# PROC010C_HD_Connector.net
KiCad netlist of a schematic drawn in Altium Designer
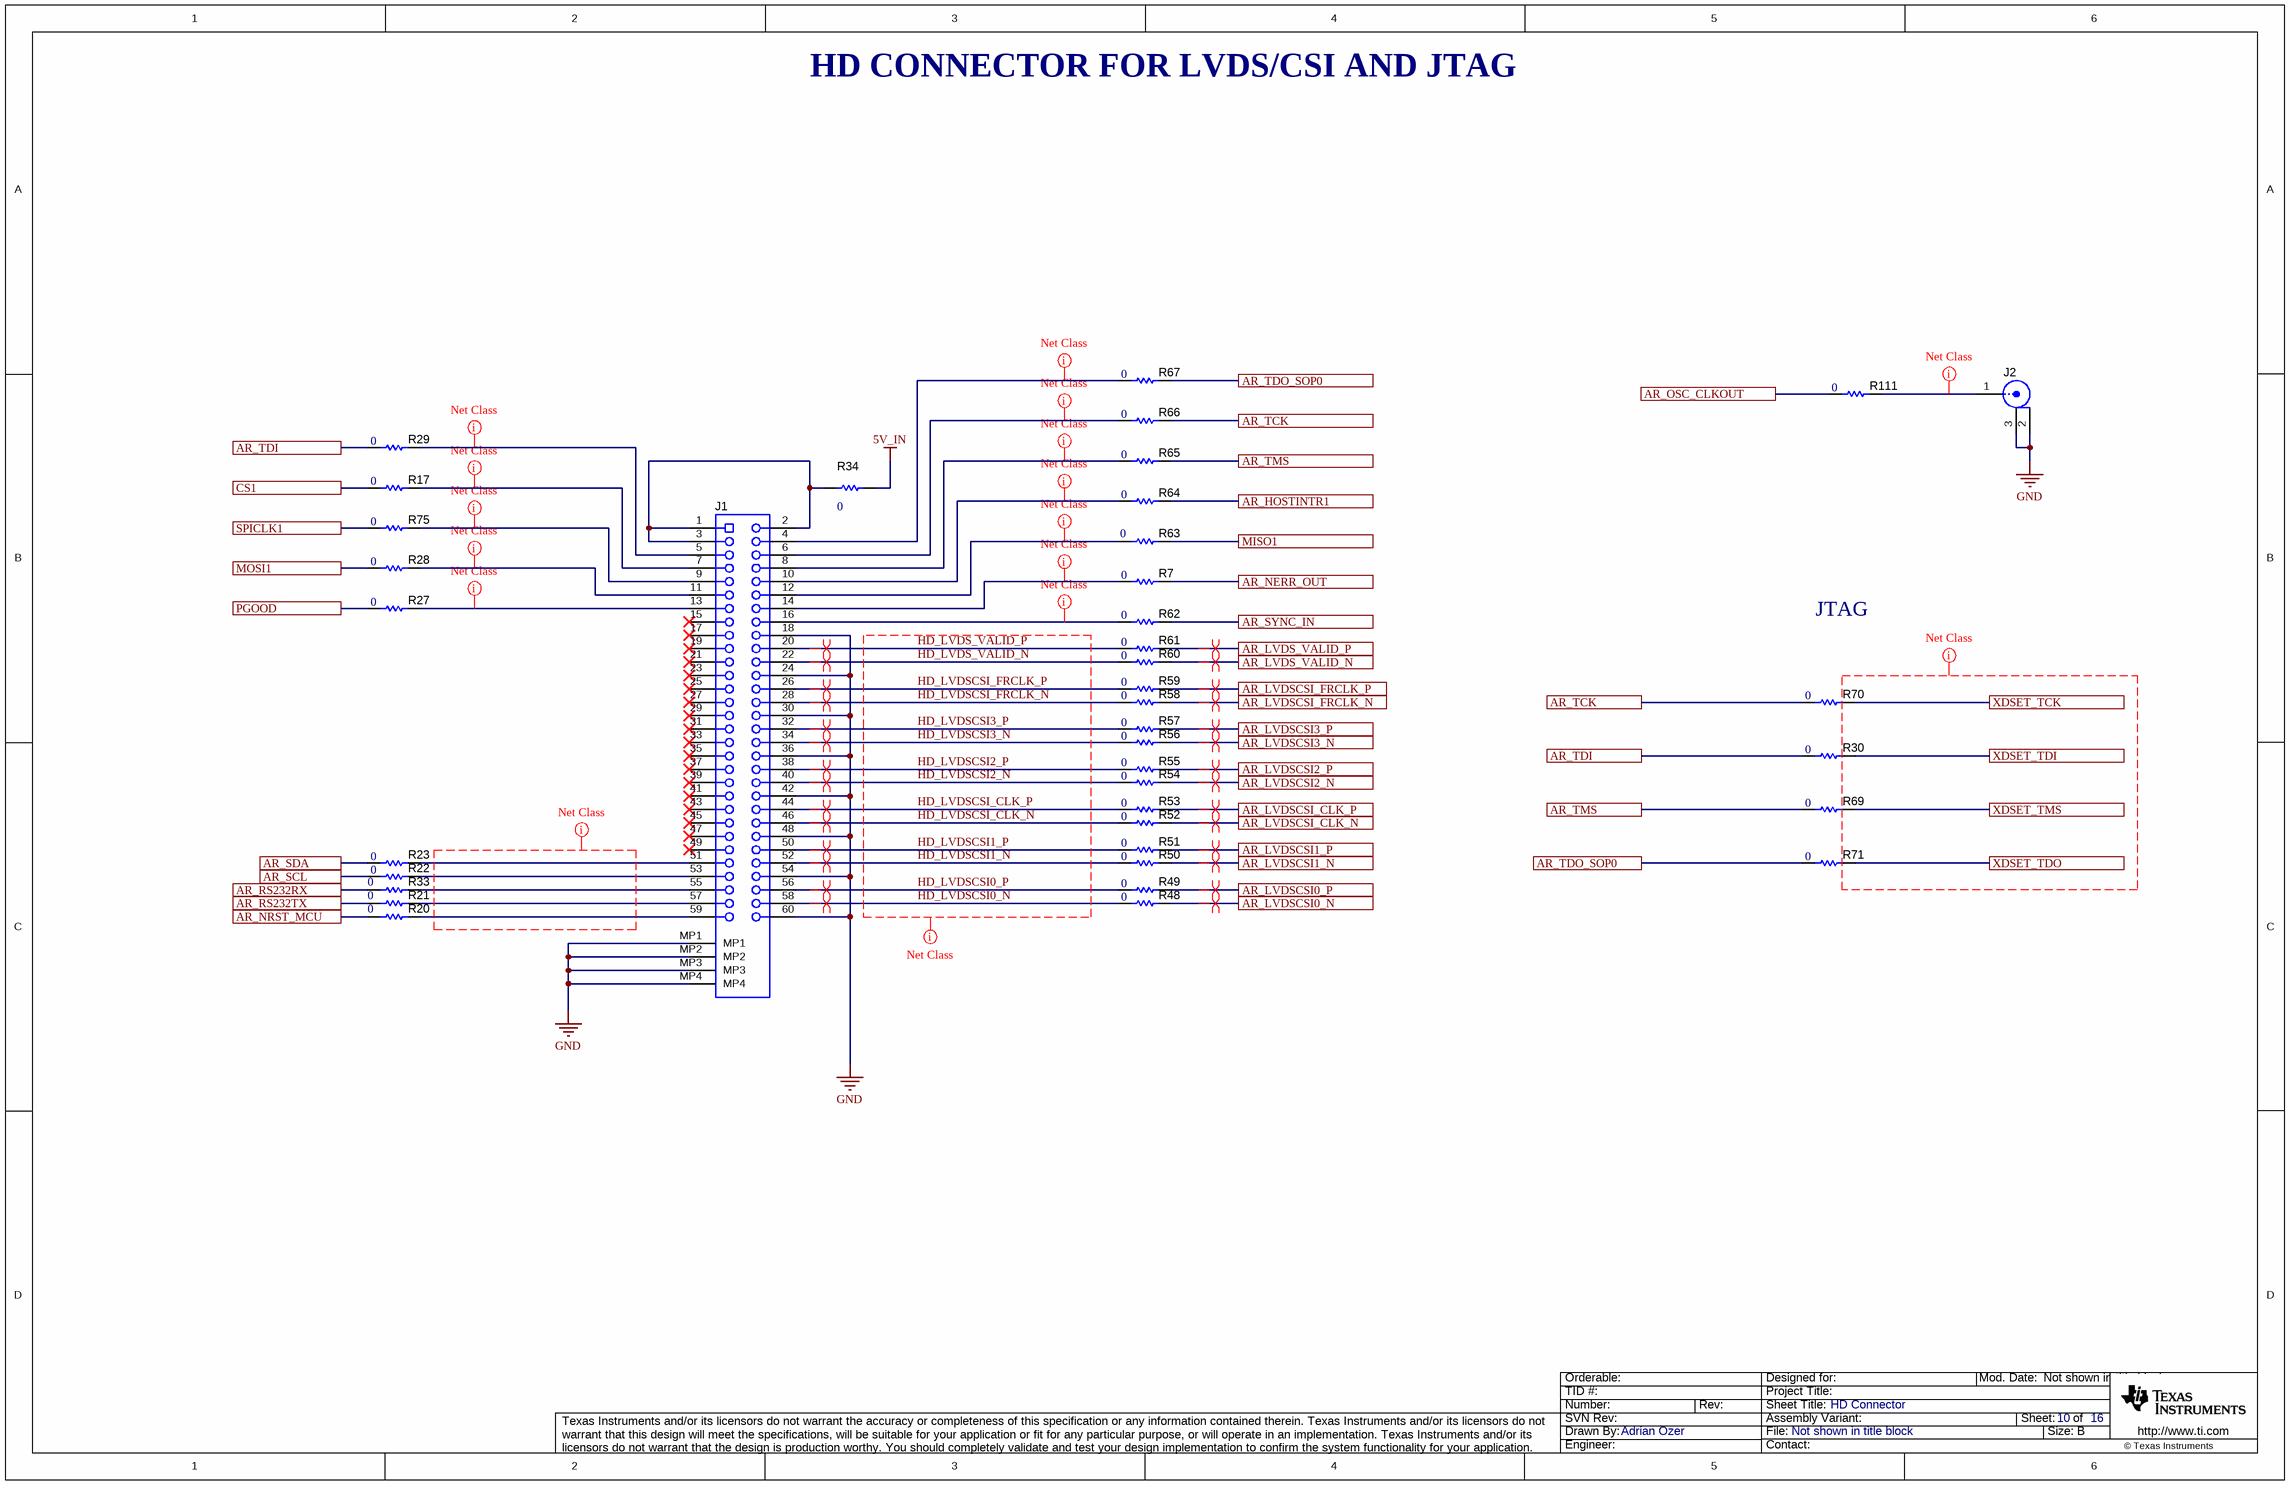
[diagram p0: PROC010C_HD Connector.SchDoc]

(export (version "E")
  (design (tool "Eeschema 10.0.6"))
  (components
    (comp (ref "J1")
      (value "QSH-030-01-L-D-A")
      (footprint "Samtec_QSH-030-01-X-D-A")
      (description "Receptacle, 0.5 mm, 30x2, Gold, TH")
      (fields (field (name "MANUFACTURER") "Samtec") (field (name "PUBLISHER") "Texas Instruments"))
      (libsource (lib "Altium Vault - TI") (part "Receptacle_30x2_4MP_LeftRight"))
    )
    (comp (ref "J2")
      (value "128-0711-201")
      (footprint "Johnson_128-0711-201")
      (description "UMC Straight Jack Receptacle, 50 Ohm, Gold, SMT")
      (fields
        (field (name "MANUFACTURER") "Cinch Connectivity")
        (field (name "PUBLISHER") "Texas Instruments")
      )
      (libsource (lib "Altium Vault - TI") (part "CMP-0055788-1"))
    )
    (comp (ref "R7")
      (value "CRCW02010000Z0ED")
      (footprint "0201_Silk")
      (description "RES, 0, 5%, 0.05 W, 0201")
      (fields (field (name "MANUFACTURER") "Vishay-Dale") (field (name "VALUEDISPLAYED") "0"))
      (libsource (lib "Altium Vault - TI") (part "Resistor"))
    )
    (comp (ref "R17")
      (value "CRCW02010000Z0ED")
      (footprint "0201_Silk")
      (description "RES, 0, 5%, 0.05 W, 0201")
      (fields (field (name "MANUFACTURER") "Vishay-Dale") (field (name "VALUEDISPLAYED") "0"))
      (libsource (lib "Altium Vault - TI") (part "Resistor"))
    )
    (comp (ref "R20")
      (value "CRCW02010000Z0ED")
      (footprint "0201_Silk")
      (description "RES, 0, 5%, 0.05 W, 0201")
      (fields (field (name "MANUFACTURER") "Vishay-Dale") (field (name "VALUEDISPLAYED") "0"))
      (libsource (lib "Altium Vault - TI") (part "Resistor"))
    )
    (comp (ref "R21")
      (value "CRCW02010000Z0ED")
      (footprint "0201_Silk")
      (description "RES, 0, 5%, 0.05 W, 0201")
      (fields (field (name "MANUFACTURER") "Vishay-Dale") (field (name "VALUEDISPLAYED") "0"))
      (libsource (lib "Altium Vault - TI") (part "Resistor"))
    )
    (comp (ref "R22")
      (value "CRCW02010000Z0ED")
      (footprint "0201_Silk")
      (description "RES, 0, 5%, 0.05 W, 0201")
      (fields (field (name "MANUFACTURER") "Vishay-Dale") (field (name "VALUEDISPLAYED") "0"))
      (libsource (lib "Altium Vault - TI") (part "Resistor"))
    )
    (comp (ref "R23")
      (value "CRCW02010000Z0ED")
      (footprint "0201_Silk")
      (description "RES, 0, 5%, 0.05 W, 0201")
      (fields (field (name "MANUFACTURER") "Vishay-Dale") (field (name "VALUEDISPLAYED") "0"))
      (libsource (lib "Altium Vault - TI") (part "Resistor"))
    )
    (comp (ref "R27")
      (value "CRCW02010000Z0ED")
      (footprint "0201_Silk")
      (description "RES, 0, 5%, 0.05 W, 0201")
      (fields (field (name "MANUFACTURER") "Vishay-Dale") (field (name "VALUEDISPLAYED") "0"))
      (libsource (lib "Altium Vault - TI") (part "Resistor"))
    )
    (comp (ref "R28")
      (value "CRCW02010000Z0ED")
      (footprint "0201_Silk")
      (description "RES, 0, 5%, 0.05 W, 0201")
      (fields (field (name "MANUFACTURER") "Vishay-Dale") (field (name "VALUEDISPLAYED") "0"))
      (libsource (lib "Altium Vault - TI") (part "Resistor"))
    )
    (comp (ref "R29")
      (value "CRCW02010000Z0ED")
      (footprint "0201_Silk")
      (description "RES, 0, 5%, 0.05 W, 0201")
      (fields (field (name "MANUFACTURER") "Vishay-Dale") (field (name "VALUEDISPLAYED") "0"))
      (libsource (lib "Altium Vault - TI") (part "Resistor"))
    )
    (comp (ref "R30")
      (value "CRCW02010000Z0ED")
      (footprint "0201_Silk")
      (description "RES, 0, 5%, 0.05 W, 0201")
      (fields (field (name "MANUFACTURER") "Vishay-Dale") (field (name "VALUEDISPLAYED") "0"))
      (libsource (lib "Altium Vault - TI") (part "Resistor"))
    )
    (comp (ref "R33")
      (value "CRCW02010000Z0ED")
      (footprint "0201_Silk")
      (description "RES, 0, 5%, 0.05 W, 0201")
      (fields (field (name "MANUFACTURER") "Vishay-Dale") (field (name "VALUEDISPLAYED") "0"))
      (libsource (lib "Altium Vault - TI") (part "Resistor"))
    )
    (comp (ref "R34")
      (value "CRCW20100000Z0EF")
      (footprint "2010L")
      (description "RES, 0, 5%, 0.75 W, AEC-Q200 Grade 0, 2010")
      (fields (field (name "MANUFACTURER") "Vishay-Dale") (field (name "VALUEDISPLAYED") "0"))
      (libsource (lib "Altium Vault - TI") (part "CMP-0016044-3"))
    )
    (comp (ref "R48")
      (value "CRCW02010000Z0ED")
      (footprint "0201_Silk")
      (description "RES, 0, 5%, 0.05 W, 0201")
      (fields (field (name "MANUFACTURER") "Vishay-Dale") (field (name "VALUEDISPLAYED") "0"))
      (libsource (lib "Altium Vault - TI") (part "Resistor"))
    )
    (comp (ref "R49")
      (value "CRCW02010000Z0ED")
      (footprint "0201_Silk")
      (description "RES, 0, 5%, 0.05 W, 0201")
      (fields (field (name "MANUFACTURER") "Vishay-Dale") (field (name "VALUEDISPLAYED") "0"))
      (libsource (lib "Altium Vault - TI") (part "Resistor"))
    )
    (comp (ref "R50")
      (value "CRCW02010000Z0ED")
      (footprint "0201_Silk")
      (description "RES, 0, 5%, 0.05 W, 0201")
      (fields (field (name "MANUFACTURER") "Vishay-Dale") (field (name "VALUEDISPLAYED") "0"))
      (libsource (lib "Altium Vault - TI") (part "Resistor"))
    )
    (comp (ref "R51")
      (value "CRCW02010000Z0ED")
      (footprint "0201_Silk")
      (description "RES, 0, 5%, 0.05 W, 0201")
      (fields (field (name "MANUFACTURER") "Vishay-Dale") (field (name "VALUEDISPLAYED") "0"))
      (libsource (lib "Altium Vault - TI") (part "Resistor"))
    )
    (comp (ref "R52")
      (value "CRCW02010000Z0ED")
      (footprint "0201_Silk")
      (description "RES, 0, 5%, 0.05 W, 0201")
      (fields (field (name "MANUFACTURER") "Vishay-Dale") (field (name "VALUEDISPLAYED") "0"))
      (libsource (lib "Altium Vault - TI") (part "Resistor"))
    )
    (comp (ref "R53")
      (value "CRCW02010000Z0ED")
      (footprint "0201_Silk")
      (description "RES, 0, 5%, 0.05 W, 0201")
      (fields (field (name "MANUFACTURER") "Vishay-Dale") (field (name "VALUEDISPLAYED") "0"))
      (libsource (lib "Altium Vault - TI") (part "Resistor"))
    )
    (comp (ref "R54")
      (value "CRCW02010000Z0ED")
      (footprint "0201_Silk")
      (description "RES, 0, 5%, 0.05 W, 0201")
      (fields (field (name "MANUFACTURER") "Vishay-Dale") (field (name "VALUEDISPLAYED") "0"))
      (libsource (lib "Altium Vault - TI") (part "Resistor"))
    )
    (comp (ref "R55")
      (value "CRCW02010000Z0ED")
      (footprint "0201_Silk")
      (description "RES, 0, 5%, 0.05 W, 0201")
      (fields (field (name "MANUFACTURER") "Vishay-Dale") (field (name "VALUEDISPLAYED") "0"))
      (libsource (lib "Altium Vault - TI") (part "Resistor"))
    )
    (comp (ref "R56")
      (value "CRCW02010000Z0ED")
      (footprint "0201_Silk")
      (description "RES, 0, 5%, 0.05 W, 0201")
      (fields (field (name "MANUFACTURER") "Vishay-Dale") (field (name "VALUEDISPLAYED") "0"))
      (libsource (lib "Altium Vault - TI") (part "Resistor"))
    )
    (comp (ref "R57")
      (value "CRCW02010000Z0ED")
      (footprint "0201_Silk")
      (description "RES, 0, 5%, 0.05 W, 0201")
      (fields (field (name "MANUFACTURER") "Vishay-Dale") (field (name "VALUEDISPLAYED") "0"))
      (libsource (lib "Altium Vault - TI") (part "Resistor"))
    )
    (comp (ref "R58")
      (value "CRCW02010000Z0ED")
      (footprint "0201_Silk")
      (description "RES, 0, 5%, 0.05 W, 0201")
      (fields (field (name "MANUFACTURER") "Vishay-Dale") (field (name "VALUEDISPLAYED") "0"))
      (libsource (lib "Altium Vault - TI") (part "Resistor"))
    )
    (comp (ref "R59")
      (value "CRCW02010000Z0ED")
      (footprint "0201_Silk")
      (description "RES, 0, 5%, 0.05 W, 0201")
      (fields (field (name "MANUFACTURER") "Vishay-Dale") (field (name "VALUEDISPLAYED") "0"))
      (libsource (lib "Altium Vault - TI") (part "Resistor"))
    )
    (comp (ref "R60")
      (value "CRCW02010000Z0ED")
      (footprint "0201_Silk")
      (description "RES, 0, 5%, 0.05 W, 0201")
      (fields (field (name "MANUFACTURER") "Vishay-Dale") (field (name "VALUEDISPLAYED") "0"))
      (libsource (lib "Altium Vault - TI") (part "Resistor"))
    )
    (comp (ref "R61")
      (value "CRCW02010000Z0ED")
      (footprint "0201_Silk")
      (description "RES, 0, 5%, 0.05 W, 0201")
      (fields (field (name "MANUFACTURER") "Vishay-Dale") (field (name "VALUEDISPLAYED") "0"))
      (libsource (lib "Altium Vault - TI") (part "Resistor"))
    )
    (comp (ref "R62")
      (value "CRCW02010000Z0ED")
      (footprint "0201_Silk")
      (description "RES, 0, 5%, 0.05 W, 0201")
      (fields (field (name "MANUFACTURER") "Vishay-Dale") (field (name "VALUEDISPLAYED") "0"))
      (libsource (lib "Altium Vault - TI") (part "Resistor"))
    )
    (comp (ref "R63")
      (value "CRCW02010000Z0ED")
      (footprint "0201_Silk")
      (description "RES, 0, 5%, 0.05 W, 0201")
      (fields (field (name "MANUFACTURER") "Vishay-Dale") (field (name "VALUEDISPLAYED") "0"))
      (libsource (lib "Altium Vault - TI") (part "Resistor"))
    )
    (comp (ref "R64")
      (value "CRCW02010000Z0ED")
      (footprint "0201_Silk")
      (description "RES, 0, 5%, 0.05 W, 0201")
      (fields (field (name "MANUFACTURER") "Vishay-Dale") (field (name "VALUEDISPLAYED") "0"))
      (libsource (lib "Altium Vault - TI") (part "Resistor"))
    )
    (comp (ref "R65")
      (value "CRCW02010000Z0ED")
      (footprint "0201_Silk")
      (description "RES, 0, 5%, 0.05 W, 0201")
      (fields (field (name "MANUFACTURER") "Vishay-Dale") (field (name "VALUEDISPLAYED") "0"))
      (libsource (lib "Altium Vault - TI") (part "Resistor"))
    )
    (comp (ref "R66")
      (value "CRCW02010000Z0ED")
      (footprint "0201_Silk")
      (description "RES, 0, 5%, 0.05 W, 0201")
      (fields (field (name "MANUFACTURER") "Vishay-Dale") (field (name "VALUEDISPLAYED") "0"))
      (libsource (lib "Altium Vault - TI") (part "Resistor"))
    )
    (comp (ref "R67")
      (value "CRCW02010000Z0ED")
      (footprint "0201_Silk")
      (description "RES, 0, 5%, 0.05 W, 0201")
      (fields (field (name "MANUFACTURER") "Vishay-Dale") (field (name "VALUEDISPLAYED") "0"))
      (libsource (lib "Altium Vault - TI") (part "Resistor"))
    )
    (comp (ref "R69")
      (value "CRCW02010000Z0ED")
      (footprint "0201_Silk")
      (description "RES, 0, 5%, 0.05 W, 0201")
      (fields (field (name "MANUFACTURER") "Vishay-Dale") (field (name "VALUEDISPLAYED") "0"))
      (libsource (lib "Altium Vault - TI") (part "Resistor"))
    )
    (comp (ref "R70")
      (value "CRCW02010000Z0ED")
      (footprint "0201_Silk")
      (description "RES, 0, 5%, 0.05 W, 0201")
      (fields (field (name "MANUFACTURER") "Vishay-Dale") (field (name "VALUEDISPLAYED") "0"))
      (libsource (lib "Altium Vault - TI") (part "Resistor"))
    )
    (comp (ref "R71")
      (value "CRCW02010000Z0ED")
      (footprint "0201_Silk")
      (description "RES, 0, 5%, 0.05 W, 0201")
      (fields (field (name "MANUFACTURER") "Vishay-Dale") (field (name "VALUEDISPLAYED") "0"))
      (libsource (lib "Altium Vault - TI") (part "Resistor"))
    )
    (comp (ref "R75")
      (value "CRCW02010000Z0ED")
      (footprint "0201_Silk")
      (description "RES, 0, 5%, 0.05 W, 0201")
      (fields (field (name "MANUFACTURER") "Vishay-Dale") (field (name "VALUEDISPLAYED") "0"))
      (libsource (lib "Altium Vault - TI") (part "Resistor"))
    )
    (comp (ref "R111")
      (value "CRCW02010000Z0ED")
      (footprint "0201_Silk")
      (description "RES, 0, 5%, 0.05 W, 0201")
      (fields (field (name "MANUFACTURER") "Vishay-Dale") (field (name "VALUEDISPLAYED") "0"))
      (libsource (lib "Altium Vault - TI") (part "Resistor"))
    )
  )
  (nets
    (net (code "1") (name "/AR_HOSTINTR1") (class "Default")
      (node (ref "R64") (pin "2") (pinfunction "2_2") (pintype "passive"))
    )
    (net (code "2") (name "/AR_LVDSCSI0_N") (class "Default")
      (node (ref "R48") (pin "2") (pinfunction "2_2") (pintype "passive"))
    )
    (net (code "3") (name "/AR_LVDSCSI0_P") (class "Default")
      (node (ref "R49") (pin "2") (pinfunction "2_2") (pintype "passive"))
    )
    (net (code "4") (name "/AR_LVDSCSI1_N") (class "Default")
      (node (ref "R50") (pin "2") (pinfunction "2_2") (pintype "passive"))
    )
    (net (code "5") (name "/AR_LVDSCSI1_P") (class "Default")
      (node (ref "R51") (pin "2") (pinfunction "2_2") (pintype "passive"))
    )
    (net (code "6") (name "/AR_LVDSCSI2_N") (class "Default")
      (node (ref "R54") (pin "2") (pinfunction "2_2") (pintype "passive"))
    )
    (net (code "7") (name "/AR_LVDSCSI2_P") (class "Default")
      (node (ref "R55") (pin "2") (pinfunction "2_2") (pintype "passive"))
    )
    (net (code "8") (name "/AR_LVDSCSI3_N") (class "Default")
      (node (ref "R56") (pin "2") (pinfunction "2_2") (pintype "passive"))
    )
    (net (code "9") (name "/AR_LVDSCSI3_P") (class "Default")
      (node (ref "R57") (pin "2") (pinfunction "2_2") (pintype "passive"))
    )
    (net (code "10") (name "/AR_LVDSCSI_CLK_N") (class "Default")
      (node (ref "R52") (pin "2") (pinfunction "2_2") (pintype "passive"))
    )
    (net (code "11") (name "/AR_LVDSCSI_CLK_P") (class "Default")
      (node (ref "R53") (pin "2") (pinfunction "2_2") (pintype "passive"))
    )
    (net (code "12") (name "/AR_LVDSCSI_FRCLK_N") (class "Default")
      (node (ref "R58") (pin "2") (pinfunction "2_2") (pintype "passive"))
    )
    (net (code "13") (name "/AR_LVDSCSI_FRCLK_P") (class "Default")
      (node (ref "R59") (pin "2") (pinfunction "2_2") (pintype "passive"))
    )
    (net (code "14") (name "/AR_LVDS_VALID_N") (class "Default")
      (node (ref "R60") (pin "2") (pinfunction "2_2") (pintype "passive"))
    )
    (net (code "15") (name "/AR_LVDS_VALID_P") (class "Default")
      (node (ref "R61") (pin "2") (pinfunction "2_2") (pintype "passive"))
    )
    (net (code "16") (name "/AR_NERR_OUT") (class "Default")
      (node (ref "R7") (pin "2") (pinfunction "2_2") (pintype "passive"))
    )
    (net (code "17") (name "/AR_NRST_MCU") (class "Default")
      (node (ref "R20") (pin "1") (pinfunction "1_1") (pintype "passive"))
    )
    (net (code "18") (name "/AR_OSC_CLKOUT") (class "Default")
      (node (ref "R111") (pin "1") (pinfunction "1_1") (pintype "passive"))
    )
    (net (code "19") (name "/AR_RS232RX") (class "Default")
      (node (ref "R33") (pin "1") (pinfunction "1_1") (pintype "passive"))
    )
    (net (code "20") (name "/AR_RS232TX") (class "Default")
      (node (ref "R21") (pin "1") (pinfunction "1_1") (pintype "passive"))
    )
    (net (code "21") (name "/AR_SCL") (class "Default")
      (node (ref "R22") (pin "1") (pinfunction "1_1") (pintype "passive"))
    )
    (net (code "22") (name "/AR_SDA") (class "Default")
      (node (ref "R23") (pin "1") (pinfunction "1_1") (pintype "passive"))
    )
    (net (code "23") (name "/AR_SYNC_IN") (class "Default")
      (node (ref "R62") (pin "2") (pinfunction "2_2") (pintype "passive"))
    )
    (net (code "24") (name "/AR_TCK") (class "Default")
      (node (ref "R66") (pin "2") (pinfunction "2_2") (pintype "passive"))
      (node (ref "R70") (pin "1") (pinfunction "1_1") (pintype "passive"))
    )
    (net (code "25") (name "/AR_TDI") (class "Default")
      (node (ref "R29") (pin "1") (pinfunction "1_1") (pintype "passive"))
      (node (ref "R30") (pin "1") (pinfunction "1_1") (pintype "passive"))
    )
    (net (code "26") (name "/AR_TDO_SOP0") (class "Default")
      (node (ref "R67") (pin "2") (pinfunction "2_2") (pintype "passive"))
      (node (ref "R71") (pin "1") (pinfunction "1_1") (pintype "passive"))
    )
    (net (code "27") (name "/AR_TMS") (class "Default")
      (node (ref "R65") (pin "2") (pinfunction "2_2") (pintype "passive"))
      (node (ref "R69") (pin "1") (pinfunction "1_1") (pintype "passive"))
    )
    (net (code "28") (name "/CS1") (class "Default")
      (node (ref "R17") (pin "1") (pinfunction "1_1") (pintype "passive"))
    )
    (net (code "29") (name "/HD_LVDSCSI0_N") (class "Default")
      (node (ref "J1") (pin "58") (pinfunction "58_58") (pintype "passive"))
      (node (ref "R48") (pin "1") (pinfunction "1_1") (pintype "passive"))
    )
    (net (code "30") (name "/HD_LVDSCSI0_P") (class "Default")
      (node (ref "J1") (pin "56") (pinfunction "56_56") (pintype "passive"))
      (node (ref "R49") (pin "1") (pinfunction "1_1") (pintype "passive"))
    )
    (net (code "31") (name "/HD_LVDSCSI1_N") (class "Default")
      (node (ref "J1") (pin "52") (pinfunction "52_52") (pintype "passive"))
      (node (ref "R50") (pin "1") (pinfunction "1_1") (pintype "passive"))
    )
    (net (code "32") (name "/HD_LVDSCSI1_P") (class "Default")
      (node (ref "J1") (pin "50") (pinfunction "50_50") (pintype "passive"))
      (node (ref "R51") (pin "1") (pinfunction "1_1") (pintype "passive"))
    )
    (net (code "33") (name "/HD_LVDSCSI2_N") (class "Default")
      (node (ref "J1") (pin "40") (pinfunction "40_40") (pintype "passive"))
      (node (ref "R54") (pin "1") (pinfunction "1_1") (pintype "passive"))
    )
    (net (code "34") (name "/HD_LVDSCSI2_P") (class "Default")
      (node (ref "J1") (pin "38") (pinfunction "38_38") (pintype "passive"))
      (node (ref "R55") (pin "1") (pinfunction "1_1") (pintype "passive"))
    )
    (net (code "35") (name "/HD_LVDSCSI3_N") (class "Default")
      (node (ref "J1") (pin "34") (pinfunction "34_34") (pintype "passive"))
      (node (ref "R56") (pin "1") (pinfunction "1_1") (pintype "passive"))
    )
    (net (code "36") (name "/HD_LVDSCSI3_P") (class "Default")
      (node (ref "J1") (pin "32") (pinfunction "32_32") (pintype "passive"))
      (node (ref "R57") (pin "1") (pinfunction "1_1") (pintype "passive"))
    )
    (net (code "37") (name "/HD_LVDSCSI_CLK_N") (class "Default")
      (node (ref "J1") (pin "46") (pinfunction "46_46") (pintype "passive"))
      (node (ref "R52") (pin "1") (pinfunction "1_1") (pintype "passive"))
    )
    (net (code "38") (name "/HD_LVDSCSI_CLK_P") (class "Default")
      (node (ref "J1") (pin "44") (pinfunction "44_44") (pintype "passive"))
      (node (ref "R53") (pin "1") (pinfunction "1_1") (pintype "passive"))
    )
    (net (code "39") (name "/HD_LVDSCSI_FRCLK_N") (class "Default")
      (node (ref "J1") (pin "28") (pinfunction "28_28") (pintype "passive"))
      (node (ref "R58") (pin "1") (pinfunction "1_1") (pintype "passive"))
    )
    (net (code "40") (name "/HD_LVDSCSI_FRCLK_P") (class "Default")
      (node (ref "J1") (pin "26") (pinfunction "26_26") (pintype "passive"))
      (node (ref "R59") (pin "1") (pinfunction "1_1") (pintype "passive"))
    )
    (net (code "41") (name "/HD_LVDS_VALID_N") (class "Default")
      (node (ref "J1") (pin "22") (pinfunction "22_22") (pintype "passive"))
      (node (ref "R60") (pin "1") (pinfunction "1_1") (pintype "passive"))
    )
    (net (code "42") (name "/HD_LVDS_VALID_P") (class "Default")
      (node (ref "J1") (pin "20") (pinfunction "20_20") (pintype "passive"))
      (node (ref "R61") (pin "1") (pinfunction "1_1") (pintype "passive"))
    )
    (net (code "43") (name "/MISO1") (class "Default")
      (node (ref "R63") (pin "2") (pinfunction "2_2") (pintype "passive"))
    )
    (net (code "44") (name "/MOSI1") (class "Default")
      (node (ref "R28") (pin "1") (pinfunction "1_1") (pintype "passive"))
    )
    (net (code "45") (name "/PGOOD") (class "Default")
      (node (ref "R27") (pin "1") (pinfunction "1_1") (pintype "passive"))
    )
    (net (code "46") (name "/SPICLK1") (class "Default")
      (node (ref "R75") (pin "1") (pinfunction "1_1") (pintype "passive"))
    )
    (net (code "47") (name "/XDSET_TCK") (class "Default")
      (node (ref "R70") (pin "2") (pinfunction "2_2") (pintype "passive"))
    )
    (net (code "48") (name "/XDSET_TDI") (class "Default")
      (node (ref "R30") (pin "2") (pinfunction "2_2") (pintype "passive"))
    )
    (net (code "49") (name "/XDSET_TDO") (class "Default")
      (node (ref "R71") (pin "2") (pinfunction "2_2") (pintype "passive"))
    )
    (net (code "50") (name "/XDSET_TMS") (class "Default")
      (node (ref "R69") (pin "2") (pinfunction "2_2") (pintype "passive"))
    )
    (net (code "51") (name "5V_IN") (class "Default")
      (node (ref "R34") (pin "2") (pinfunction "2_2") (pintype "passive"))
    )
    (net (code "52") (name "GND") (class "Default")
      (node (ref "J1") (pin "18") (pinfunction "18_18") (pintype "passive"))
      (node (ref "J1") (pin "24") (pinfunction "24_24") (pintype "passive"))
      (node (ref "J1") (pin "30") (pinfunction "30_30") (pintype "passive"))
      (node (ref "J1") (pin "36") (pinfunction "36_36") (pintype "passive"))
      (node (ref "J1") (pin "42") (pinfunction "42_42") (pintype "passive"))
      (node (ref "J1") (pin "48") (pinfunction "48_48") (pintype "passive"))
      (node (ref "J1") (pin "54") (pinfunction "54_54") (pintype "passive"))
      (node (ref "J1") (pin "60") (pinfunction "60_60") (pintype "passive"))
      (node (ref "J1") (pin "MP1") (pinfunction "MP1_MP1") (pintype "passive"))
      (node (ref "J1") (pin "MP2") (pinfunction "MP2_MP2") (pintype "passive"))
      (node (ref "J1") (pin "MP3") (pinfunction "MP3_MP3") (pintype "passive"))
      (node (ref "J1") (pin "MP4") (pinfunction "MP4_MP4") (pintype "passive"))
      (node (ref "J2") (pin "2") (pinfunction "2_2") (pintype "passive"))
      (node (ref "J2") (pin "3") (pinfunction "3_3") (pintype "passive"))
    )
    (net (code "53") (name "Net-(J1-Pad1)") (class "Default")
      (node (ref "J1") (pin "1") (pinfunction "1_1") (pintype "passive"))
      (node (ref "J1") (pin "2") (pinfunction "2_2") (pintype "passive"))
      (node (ref "J1") (pin "3") (pinfunction "3_3") (pintype "passive"))
      (node (ref "R34") (pin "1") (pinfunction "1_1") (pintype "passive"))
    )
    (net (code "54") (name "Net-(J1-Pad4)") (class "Default")
      (node (ref "J1") (pin "4") (pinfunction "4_4") (pintype "passive"))
      (node (ref "R67") (pin "1") (pinfunction "1_1") (pintype "passive"))
    )
    (net (code "55") (name "Net-(J1-Pad5)") (class "Default")
      (node (ref "J1") (pin "5") (pinfunction "5_5") (pintype "passive"))
      (node (ref "R29") (pin "2") (pinfunction "2_2") (pintype "passive"))
    )
    (net (code "56") (name "Net-(J1-Pad6)") (class "Default")
      (node (ref "J1") (pin "6") (pinfunction "6_6") (pintype "passive"))
      (node (ref "R66") (pin "1") (pinfunction "1_1") (pintype "passive"))
    )
    (net (code "57") (name "Net-(J1-Pad7)") (class "Default")
      (node (ref "J1") (pin "7") (pinfunction "7_7") (pintype "passive"))
      (node (ref "R17") (pin "2") (pinfunction "2_2") (pintype "passive"))
    )
    (net (code "58") (name "Net-(J1-Pad8)") (class "Default")
      (node (ref "J1") (pin "8") (pinfunction "8_8") (pintype "passive"))
      (node (ref "R65") (pin "1") (pinfunction "1_1") (pintype "passive"))
    )
    (net (code "59") (name "Net-(J1-Pad9)") (class "Default")
      (node (ref "J1") (pin "9") (pinfunction "9_9") (pintype "passive"))
      (node (ref "R75") (pin "2") (pinfunction "2_2") (pintype "passive"))
    )
    (net (code "60") (name "Net-(J1-Pad10)") (class "Default")
      (node (ref "J1") (pin "10") (pinfunction "10_10") (pintype "passive"))
      (node (ref "R64") (pin "1") (pinfunction "1_1") (pintype "passive"))
    )
    (net (code "61") (name "Net-(J1-Pad11)") (class "Default")
      (node (ref "J1") (pin "11") (pinfunction "11_11") (pintype "passive"))
      (node (ref "R28") (pin "2") (pinfunction "2_2") (pintype "passive"))
    )
    (net (code "62") (name "Net-(J1-Pad12)") (class "Default")
      (node (ref "J1") (pin "12") (pinfunction "12_12") (pintype "passive"))
      (node (ref "R63") (pin "1") (pinfunction "1_1") (pintype "passive"))
    )
    (net (code "63") (name "Net-(J1-Pad13)") (class "Default")
      (node (ref "J1") (pin "13") (pinfunction "13_13") (pintype "passive"))
      (node (ref "R27") (pin "2") (pinfunction "2_2") (pintype "passive"))
    )
    (net (code "64") (name "Net-(J1-Pad14)") (class "Default")
      (node (ref "J1") (pin "14") (pinfunction "14_14") (pintype "passive"))
      (node (ref "R7") (pin "1") (pinfunction "1_1") (pintype "passive"))
    )
    (net (code "65") (name "Net-(J1-Pad16)") (class "Default")
      (node (ref "J1") (pin "16") (pinfunction "16_16") (pintype "passive"))
      (node (ref "R62") (pin "1") (pinfunction "1_1") (pintype "passive"))
    )
    (net (code "66") (name "Net-(J1-Pad51)") (class "Default")
      (node (ref "J1") (pin "51") (pinfunction "51_51") (pintype "passive"))
      (node (ref "R23") (pin "2") (pinfunction "2_2") (pintype "passive"))
    )
    (net (code "67") (name "Net-(J1-Pad53)") (class "Default")
      (node (ref "J1") (pin "53") (pinfunction "53_53") (pintype "passive"))
      (node (ref "R22") (pin "2") (pinfunction "2_2") (pintype "passive"))
    )
    (net (code "68") (name "Net-(J1-Pad55)") (class "Default")
      (node (ref "J1") (pin "55") (pinfunction "55_55") (pintype "passive"))
      (node (ref "R33") (pin "2") (pinfunction "2_2") (pintype "passive"))
    )
    (net (code "69") (name "Net-(J1-Pad57)") (class "Default")
      (node (ref "J1") (pin "57") (pinfunction "57_57") (pintype "passive"))
      (node (ref "R21") (pin "2") (pinfunction "2_2") (pintype "passive"))
    )
    (net (code "70") (name "Net-(J1-Pad59)") (class "Default")
      (node (ref "J1") (pin "59") (pinfunction "59_59") (pintype "passive"))
      (node (ref "R20") (pin "2") (pinfunction "2_2") (pintype "passive"))
    )
    (net (code "71") (name "Net-(J2-Pad1)") (class "Default")
      (node (ref "J2") (pin "1") (pinfunction "1_1") (pintype "passive"))
      (node (ref "R111") (pin "2") (pinfunction "2_2") (pintype "passive"))
    )
    (net (code "72") (name "unconnected-(J1-Pad15)") (class "Default")
      (node (ref "J1") (pin "15") (pinfunction "15_15") (pintype "passive+no_connect"))
    )
    (net (code "73") (name "unconnected-(J1-Pad17)") (class "Default")
      (node (ref "J1") (pin "17") (pinfunction "17_17") (pintype "passive+no_connect"))
    )
    (net (code "74") (name "unconnected-(J1-Pad19)") (class "Default")
      (node (ref "J1") (pin "19") (pinfunction "19_19") (pintype "passive+no_connect"))
    )
    (net (code "75") (name "unconnected-(J1-Pad21)") (class "Default")
      (node (ref "J1") (pin "21") (pinfunction "21_21") (pintype "passive+no_connect"))
    )
    (net (code "76") (name "unconnected-(J1-Pad23)") (class "Default")
      (node (ref "J1") (pin "23") (pinfunction "23_23") (pintype "passive+no_connect"))
    )
    (net (code "77") (name "unconnected-(J1-Pad25)") (class "Default")
      (node (ref "J1") (pin "25") (pinfunction "25_25") (pintype "passive+no_connect"))
    )
    (net (code "78") (name "unconnected-(J1-Pad27)") (class "Default")
      (node (ref "J1") (pin "27") (pinfunction "27_27") (pintype "passive+no_connect"))
    )
    (net (code "79") (name "unconnected-(J1-Pad29)") (class "Default")
      (node (ref "J1") (pin "29") (pinfunction "29_29") (pintype "passive+no_connect"))
    )
    (net (code "80") (name "unconnected-(J1-Pad31)") (class "Default")
      (node (ref "J1") (pin "31") (pinfunction "31_31") (pintype "passive+no_connect"))
    )
    (net (code "81") (name "unconnected-(J1-Pad33)") (class "Default")
      (node (ref "J1") (pin "33") (pinfunction "33_33") (pintype "passive+no_connect"))
    )
    (net (code "82") (name "unconnected-(J1-Pad35)") (class "Default")
      (node (ref "J1") (pin "35") (pinfunction "35_35") (pintype "passive+no_connect"))
    )
    (net (code "83") (name "unconnected-(J1-Pad37)") (class "Default")
      (node (ref "J1") (pin "37") (pinfunction "37_37") (pintype "passive+no_connect"))
    )
    (net (code "84") (name "unconnected-(J1-Pad39)") (class "Default")
      (node (ref "J1") (pin "39") (pinfunction "39_39") (pintype "passive+no_connect"))
    )
    (net (code "85") (name "unconnected-(J1-Pad41)") (class "Default")
      (node (ref "J1") (pin "41") (pinfunction "41_41") (pintype "passive+no_connect"))
    )
    (net (code "86") (name "unconnected-(J1-Pad43)") (class "Default")
      (node (ref "J1") (pin "43") (pinfunction "43_43") (pintype "passive+no_connect"))
    )
    (net (code "87") (name "unconnected-(J1-Pad45)") (class "Default")
      (node (ref "J1") (pin "45") (pinfunction "45_45") (pintype "passive+no_connect"))
    )
    (net (code "88") (name "unconnected-(J1-Pad47)") (class "Default")
      (node (ref "J1") (pin "47") (pinfunction "47_47") (pintype "passive+no_connect"))
    )
    (net (code "89") (name "unconnected-(J1-Pad49)") (class "Default")
      (node (ref "J1") (pin "49") (pinfunction "49_49") (pintype "passive+no_connect"))
    )
  )
)
